# sch1.net
KiCad netlist of a schematic drawn in EAGLE
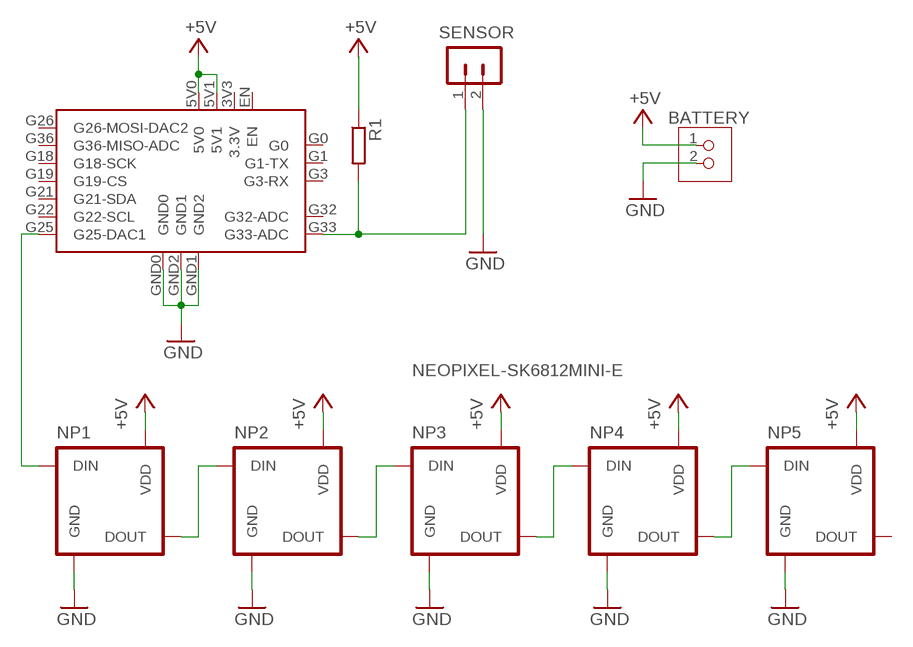
[diagram p0: schematic, sheet 1]

(export (version "E")
  (design (tool "Eeschema 10.0.6"))
  (components
    (comp (ref "M5PICO1")
      (value "M5STAMP-PICO")
      (footprint "eagle-import:M5STAMP-PICO")
      (libsource (lib "eagle-import") (part "M5STAMP-PICO"))
    )
    (comp (ref "NP1")
      (value "NEOPIXEL-SK6812MINI-E")
      (footprint "eagle-import:SK6812MINI-E")
      (libsource (lib "eagle-import") (part "NEOPIXEL-SK6812MINI-E"))
    )
    (comp (ref "NP2")
      (value "NEOPIXEL-SK6812MINI-E")
      (footprint "eagle-import:SK6812MINI-E")
      (libsource (lib "eagle-import") (part "NEOPIXEL-SK6812MINI-E"))
    )
    (comp (ref "NP3")
      (value "NEOPIXEL-SK6812MINI-E")
      (footprint "eagle-import:SK6812MINI-E")
      (libsource (lib "eagle-import") (part "NEOPIXEL-SK6812MINI-E"))
    )
    (comp (ref "NP4")
      (value "NEOPIXEL-SK6812MINI-E")
      (footprint "eagle-import:SK6812MINI-E")
      (libsource (lib "eagle-import") (part "NEOPIXEL-SK6812MINI-E"))
    )
    (comp (ref "NP5")
      (value "NEOPIXEL-SK6812MINI-E")
      (footprint "eagle-import:SK6812MINI-E")
      (libsource (lib "eagle-import") (part "NEOPIXEL-SK6812MINI-E"))
    )
    (comp (ref "P1")
      (value "BATTERY")
      (footprint "eagle-import:JST-PH2")
      (libsource (lib "eagle-import") (part "JST-PH2"))
    )
    (comp (ref "R1")
      (value "R-EU_0204/7")
      (footprint "eagle-import:0204_7")
      (libsource (lib "eagle-import") (part "R-EU_0204/7"))
    )
    (comp (ref "SV1")
      (value "SENSOR")
      (footprint "eagle-import:PINHEAD-MA02-1")
      (libsource (lib "eagle-import") (part "PINHEAD-MA02-1"))
    )
  )
  (nets
    (net (code "1") (name "+5V") (class "Default")
      (node (ref "M5PICO1") (pin "5V0") (pinfunction "5V0_5V0") (pintype "bidirectional"))
      (node (ref "M5PICO1") (pin "5V1") (pinfunction "5V1_5V1") (pintype "bidirectional"))
      (node (ref "NP1") (pin "VDD") (pinfunction "VDD_VDD") (pintype "bidirectional"))
      (node (ref "NP2") (pin "VDD") (pinfunction "VDD_VDD") (pintype "bidirectional"))
      (node (ref "NP3") (pin "VDD") (pinfunction "VDD_VDD") (pintype "bidirectional"))
      (node (ref "NP4") (pin "VDD") (pinfunction "VDD_VDD") (pintype "bidirectional"))
      (node (ref "NP5") (pin "VDD") (pinfunction "VDD_VDD") (pintype "bidirectional"))
      (node (ref "P1") (pin "1") (pinfunction "1_1") (pintype "passive"))
      (node (ref "R1") (pin "1") (pinfunction "1_1") (pintype "passive"))
    )
    (net (code "2") (name "GND") (class "Default")
      (node (ref "M5PICO1") (pin "GND0") (pinfunction "GND0_GND0") (pintype "bidirectional"))
      (node (ref "M5PICO1") (pin "GND1") (pinfunction "GND2_GND1") (pintype "bidirectional"))
      (node (ref "M5PICO1") (pin "GND2") (pinfunction "GND1_GND2") (pintype "bidirectional"))
      (node (ref "NP1") (pin "GND") (pinfunction "GND_GND") (pintype "bidirectional"))
      (node (ref "NP2") (pin "GND") (pinfunction "GND_GND") (pintype "bidirectional"))
      (node (ref "NP3") (pin "GND") (pinfunction "GND_GND") (pintype "bidirectional"))
      (node (ref "NP4") (pin "GND") (pinfunction "GND_GND") (pintype "bidirectional"))
      (node (ref "NP5") (pin "GND") (pinfunction "GND_GND") (pintype "bidirectional"))
      (node (ref "P1") (pin "2") (pinfunction "2_2") (pintype "passive"))
      (node (ref "SV1") (pin "2") (pinfunction "2_2") (pintype "passive"))
    )
    (net (code "3") (name "Net-(M5PICO1-G25-DAC1)") (class "Default")
      (node (ref "M5PICO1") (pin "G25") (pinfunction "G25-DAC1_G25") (pintype "bidirectional"))
      (node (ref "NP1") (pin "DIN") (pinfunction "DIN_DIN") (pintype "input"))
    )
    (net (code "4") (name "Net-(M5PICO1-G33-ADC)") (class "Default")
      (node (ref "M5PICO1") (pin "G33") (pinfunction "G33-ADC_G33") (pintype "bidirectional"))
      (node (ref "R1") (pin "2") (pinfunction "2_2") (pintype "passive"))
      (node (ref "SV1") (pin "1") (pinfunction "1_1") (pintype "passive"))
    )
    (net (code "5") (name "Net-(NP1-PadDOUT)") (class "Default")
      (node (ref "NP1") (pin "DOUT") (pinfunction "DOUT_DOUT") (pintype "output"))
      (node (ref "NP2") (pin "DIN") (pinfunction "DIN_DIN") (pintype "input"))
    )
    (net (code "6") (name "Net-(NP2-PadDOUT)") (class "Default")
      (node (ref "NP2") (pin "DOUT") (pinfunction "DOUT_DOUT") (pintype "output"))
      (node (ref "NP3") (pin "DIN") (pinfunction "DIN_DIN") (pintype "input"))
    )
    (net (code "7") (name "Net-(NP3-PadDOUT)") (class "Default")
      (node (ref "NP3") (pin "DOUT") (pinfunction "DOUT_DOUT") (pintype "output"))
      (node (ref "NP4") (pin "DIN") (pinfunction "DIN_DIN") (pintype "input"))
    )
    (net (code "8") (name "Net-(NP4-PadDOUT)") (class "Default")
      (node (ref "NP4") (pin "DOUT") (pinfunction "DOUT_DOUT") (pintype "output"))
      (node (ref "NP5") (pin "DIN") (pinfunction "DIN_DIN") (pintype "input"))
    )
    (net (code "9") (name "unconnected-(M5PICO1-3.3V-Pad3V3)") (class "Default")
      (node (ref "M5PICO1") (pin "3V3") (pinfunction "3.3V_3V3") (pintype "bidirectional"))
    )
    (net (code "10") (name "unconnected-(M5PICO1-G1-TX-PadG1)") (class "Default")
      (node (ref "M5PICO1") (pin "G1") (pinfunction "G1-TX_G1") (pintype "bidirectional"))
    )
    (net (code "11") (name "unconnected-(M5PICO1-G3-RX-PadG3)") (class "Default")
      (node (ref "M5PICO1") (pin "G3") (pinfunction "G3-RX_G3") (pintype "bidirectional"))
    )
    (net (code "12") (name "unconnected-(M5PICO1-G18-SCK-PadG18)") (class "Default")
      (node (ref "M5PICO1") (pin "G18") (pinfunction "G18-SCK_G18") (pintype "bidirectional"))
    )
    (net (code "13") (name "unconnected-(M5PICO1-G19-CS-PadG19)") (class "Default")
      (node (ref "M5PICO1") (pin "G19") (pinfunction "G19-CS_G19") (pintype "bidirectional"))
    )
    (net (code "14") (name "unconnected-(M5PICO1-G21-SDA-PadG21)") (class "Default")
      (node (ref "M5PICO1") (pin "G21") (pinfunction "G21-SDA_G21") (pintype "bidirectional"))
    )
    (net (code "15") (name "unconnected-(M5PICO1-G22-SCL-PadG22)") (class "Default")
      (node (ref "M5PICO1") (pin "G22") (pinfunction "G22-SCL_G22") (pintype "bidirectional"))
    )
    (net (code "16") (name "unconnected-(M5PICO1-G26-MOSI-DAC2-PadG26)") (class "Default")
      (node (ref "M5PICO1") (pin "G26") (pinfunction "G26-MOSI-DAC2_G26") (pintype "bidirectional"))
    )
    (net (code "17") (name "unconnected-(M5PICO1-G32-ADC-PadG32)") (class "Default")
      (node (ref "M5PICO1") (pin "G32") (pinfunction "G32-ADC_G32") (pintype "bidirectional"))
    )
    (net (code "18") (name "unconnected-(M5PICO1-G36-MISO-ADC-PadG36)") (class "Default")
      (node (ref "M5PICO1") (pin "G36") (pinfunction "G36-MISO-ADC_G36") (pintype "bidirectional"))
    )
    (net (code "19") (name "unconnected-(M5PICO1-PadEN)") (class "Default")
      (node (ref "M5PICO1") (pin "EN") (pinfunction "EN_EN") (pintype "bidirectional"))
    )
    (net (code "20") (name "unconnected-(M5PICO1-PadG0)") (class "Default")
      (node (ref "M5PICO1") (pin "G0") (pinfunction "G0_G0") (pintype "bidirectional"))
    )
    (net (code "21") (name "unconnected-(NP5-PadDOUT)") (class "Default")
      (node (ref "NP5") (pin "DOUT") (pinfunction "DOUT_DOUT") (pintype "output"))
    )
  )
)
